# LED_Circuit.net
KiCad netlist of a schematic drawn in Altium Designer
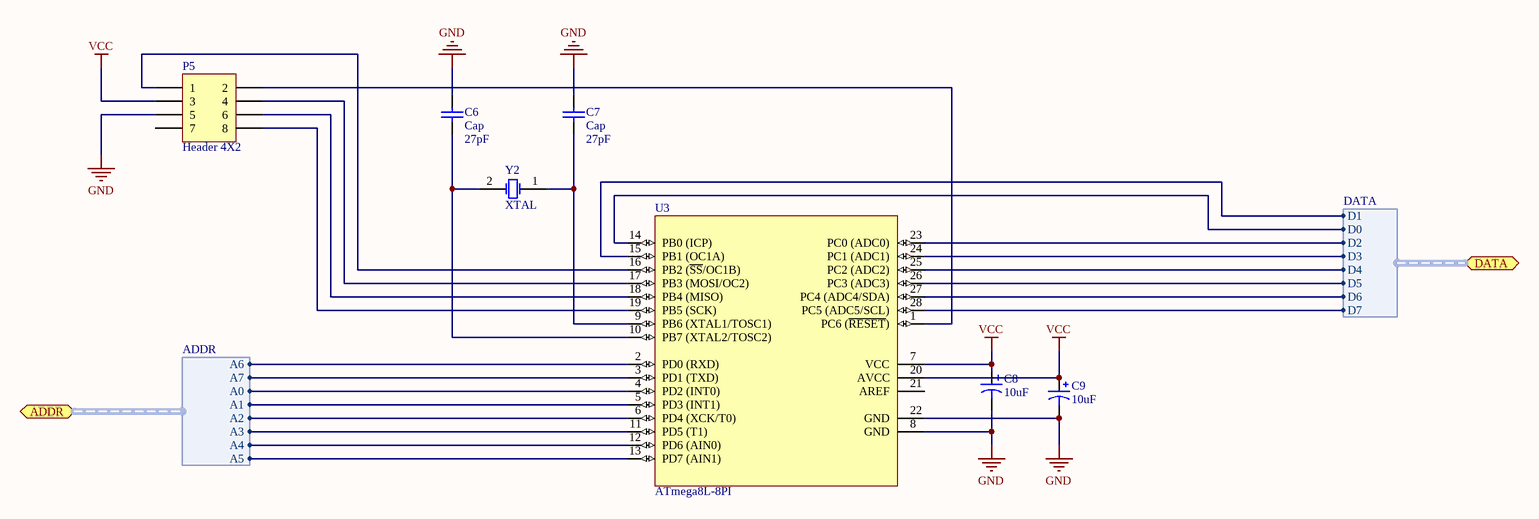
[diagram p0: LED Circuit.SchDoc]

(export (version "E")
  (design (tool "Eeschema 10.0.6"))
  (components
    (comp (ref "C6")
      (value "Cap")
      (footprint "CAPR2.54-5.1x3.2")
      (description "Capacitor")
      (fields (field (name "ALTIUM_VALUE") "27pF") (field (name "PUBLISHER") "Altium Limited"))
      (libsource (lib "Miscellaneous Devices") (part "Cap"))
    )
    (comp (ref "C7")
      (value "Cap")
      (footprint "CAPR2.54-5.1x3.2")
      (description "Capacitor")
      (fields (field (name "ALTIUM_VALUE") "27pF") (field (name "PUBLISHER") "Altium Limited"))
      (libsource (lib "Miscellaneous Devices") (part "Cap"))
    )
    (comp (ref "C8")
      (value "10uF")
      (footprint "CAPPR1.5-4x5")
      (description "Polarized Capacitor (Radial)")
      (fields (field (name "Comment") "Cap Pol1") (field (name "PUBLISHER") "Altium Limited"))
      (libsource (lib "Miscellaneous Devices") (part "Cap Pol1"))
    )
    (comp (ref "C9")
      (value "10uF")
      (footprint "CAPPR1.5-4x5")
      (description "Polarized Capacitor (Radial)")
      (fields (field (name "Comment") "Cap Pol1") (field (name "PUBLISHER") "Altium Limited"))
      (libsource (lib "Miscellaneous Devices") (part "Cap Pol1"))
    )
    (comp (ref "P5")
      (value "Header 4X2")
      (footprint "HDR2X4")
      (description "Header, 4-Pin, Dual row")
      (fields (field (name "PUBLISHER") "Altium Limited"))
      (libsource (lib "Miscellaneous Connectors") (part "Header 4X2"))
    )
    (comp (ref "U3")
      (value "ATmega8L-8PI")
      (footprint "28P3")
      (description "8-Bit AVR Microcontroller with 8K Bytes of In-System Programmable Flash Memory")
      (fields (field (name "PUBLISHER") "Altium Limited"))
      (libsource (lib "Atmel Microcontroller 8-Bit AVR") (part "ATmega8L-8PI"))
    )
    (comp (ref "Y2")
      (value "XTAL")
      (footprint "Crystal Oscillator")
      (libsource (lib "Components") (part "Crystal Oscillator"))
    )
  )
  (nets
    (net (code "3") (name "/A0") (class "Default")
      (node (ref "U3") (pin "4") (pinfunction "PD2_(INT0)_4") (pintype "bidirectional"))
    )
    (net (code "4") (name "/A1") (class "Default")
      (node (ref "U3") (pin "5") (pinfunction "PD3_(INT1)_5") (pintype "bidirectional"))
    )
    (net (code "5") (name "/A2") (class "Default")
      (node (ref "U3") (pin "6") (pinfunction "PD4_(XCK/T0)_6") (pintype "bidirectional"))
    )
    (net (code "6") (name "/A3") (class "Default")
      (node (ref "U3") (pin "11") (pinfunction "PD5_(T1)_11") (pintype "bidirectional"))
    )
    (net (code "7") (name "/A4") (class "Default")
      (node (ref "U3") (pin "12") (pinfunction "PD6_(AIN0)_12") (pintype "bidirectional"))
    )
    (net (code "8") (name "/A5") (class "Default")
      (node (ref "U3") (pin "13") (pinfunction "PD7_(AIN1)_13") (pintype "bidirectional"))
    )
    (net (code "9") (name "/A6") (class "Default")
      (node (ref "U3") (pin "2") (pinfunction "PD0_(RXD)_2") (pintype "bidirectional"))
    )
    (net (code "10") (name "/A7") (class "Default")
      (node (ref "U3") (pin "3") (pinfunction "PD1_(TXD)_3") (pintype "bidirectional"))
    )
    (net (code "11") (name "/D0") (class "Default")
      (node (ref "U3") (pin "14") (pinfunction "PB0_(ICP)_14") (pintype "bidirectional"))
    )
    (net (code "12") (name "/D1") (class "Default")
      (node (ref "U3") (pin "15") (pinfunction "PB1_(OC1A)_15") (pintype "bidirectional"))
    )
    (net (code "13") (name "/D2") (class "Default")
      (node (ref "U3") (pin "23") (pinfunction "PC0_(ADC0)_23") (pintype "bidirectional"))
    )
    (net (code "14") (name "/D3") (class "Default")
      (node (ref "U3") (pin "24") (pinfunction "PC1_(ADC1)_24") (pintype "bidirectional"))
    )
    (net (code "15") (name "/D4") (class "Default")
      (node (ref "U3") (pin "25") (pinfunction "PC2_(ADC2)_25") (pintype "bidirectional"))
    )
    (net (code "16") (name "/D5") (class "Default")
      (node (ref "U3") (pin "26") (pinfunction "PC3_(ADC3)_26") (pintype "bidirectional"))
    )
    (net (code "17") (name "/D6") (class "Default")
      (node (ref "U3") (pin "27") (pinfunction "PC4_(ADC4/SDA)_27") (pintype "bidirectional"))
    )
    (net (code "18") (name "/D7") (class "Default")
      (node (ref "U3") (pin "28") (pinfunction "PC5_(ADC5/SCL)_28") (pintype "bidirectional"))
    )
    (net (code "21") (name "GND") (class "Default")
      (node (ref "C6") (pin "2") (pinfunction "2_2") (pintype "passive"))
      (node (ref "C7") (pin "2") (pinfunction "2_2") (pintype "passive"))
      (node (ref "C8") (pin "2") (pinfunction "2_2") (pintype "passive"))
      (node (ref "C9") (pin "2") (pinfunction "2_2") (pintype "passive"))
      (node (ref "P5") (pin "5") (pinfunction "5_5") (pintype "passive"))
      (node (ref "U3") (pin "22") (pinfunction "GND_22") (pintype "power_in"))
      (node (ref "U3") (pin "8") (pinfunction "GND_8") (pintype "power_in"))
    )
    (net (code "22") (name "Net-(U3-PB2_(~{SS}{slash}OC1B))") (class "Default")
      (node (ref "P5") (pin "1") (pinfunction "1_1") (pintype "passive"))
      (node (ref "U3") (pin "16") (pinfunction "PB2_(~{SS}/OC1B)_16") (pintype "bidirectional"))
    )
    (net (code "23") (name "Net-(U3-PB3_(MOSI{slash}OC2))") (class "Default")
      (node (ref "P5") (pin "4") (pinfunction "4_4") (pintype "passive"))
      (node (ref "U3") (pin "17") (pinfunction "PB3_(MOSI/OC2)_17") (pintype "bidirectional"))
    )
    (net (code "24") (name "Net-(U3-PB4_(MISO))") (class "Default")
      (node (ref "P5") (pin "6") (pinfunction "6_6") (pintype "passive"))
      (node (ref "U3") (pin "18") (pinfunction "PB4_(MISO)_18") (pintype "bidirectional"))
    )
    (net (code "25") (name "Net-(U3-PB5_(SCK))") (class "Default")
      (node (ref "P5") (pin "8") (pinfunction "8_8") (pintype "passive"))
      (node (ref "U3") (pin "19") (pinfunction "PB5_(SCK)_19") (pintype "bidirectional"))
    )
    (net (code "26") (name "Net-(U3-PB6_(XTAL1{slash}TOSC1))") (class "Default")
      (node (ref "C7") (pin "1") (pinfunction "1_1") (pintype "passive"))
      (node (ref "U3") (pin "9") (pinfunction "PB6_(XTAL1/TOSC1)_9") (pintype "bidirectional"))
      (node (ref "Y2") (pin "1") (pinfunction "OSC1_1") (pintype "passive"))
    )
    (net (code "27") (name "Net-(U3-PB7_(XTAL2{slash}TOSC2))") (class "Default")
      (node (ref "C6") (pin "1") (pinfunction "1_1") (pintype "passive"))
      (node (ref "U3") (pin "10") (pinfunction "PB7_(XTAL2/TOSC2)_10") (pintype "bidirectional"))
      (node (ref "Y2") (pin "2") (pinfunction "OSC2_2") (pintype "passive"))
    )
    (net (code "28") (name "Net-(U3-PC6_(~{RESET}))") (class "Default")
      (node (ref "P5") (pin "2") (pinfunction "2_2") (pintype "passive"))
      (node (ref "U3") (pin "1") (pinfunction "PC6_(~{RESET})_1") (pintype "bidirectional"))
    )
    (net (code "29") (name "VCC") (class "Default")
      (node (ref "C8") (pin "1") (pinfunction "1_1") (pintype "passive"))
      (node (ref "C9") (pin "1") (pinfunction "1_1") (pintype "passive"))
      (node (ref "P5") (pin "3") (pinfunction "3_3") (pintype "passive"))
      (node (ref "U3") (pin "20") (pinfunction "AVCC_20") (pintype "power_in"))
      (node (ref "U3") (pin "7") (pinfunction "VCC_7") (pintype "power_in"))
    )
    (net (code "30") (name "unconnected-(P5-Pad7)") (class "Default")
      (node (ref "P5") (pin "7") (pinfunction "7_7") (pintype "passive"))
    )
    (net (code "31") (name "unconnected-(U3-AREF-Pad21)") (class "Default")
      (node (ref "U3") (pin "21") (pinfunction "AREF_21") (pintype "passive"))
    )
  )
)
